# AC_Measurev2_250616.net
KiCad netlist of a schematic drawn in Altium Designer
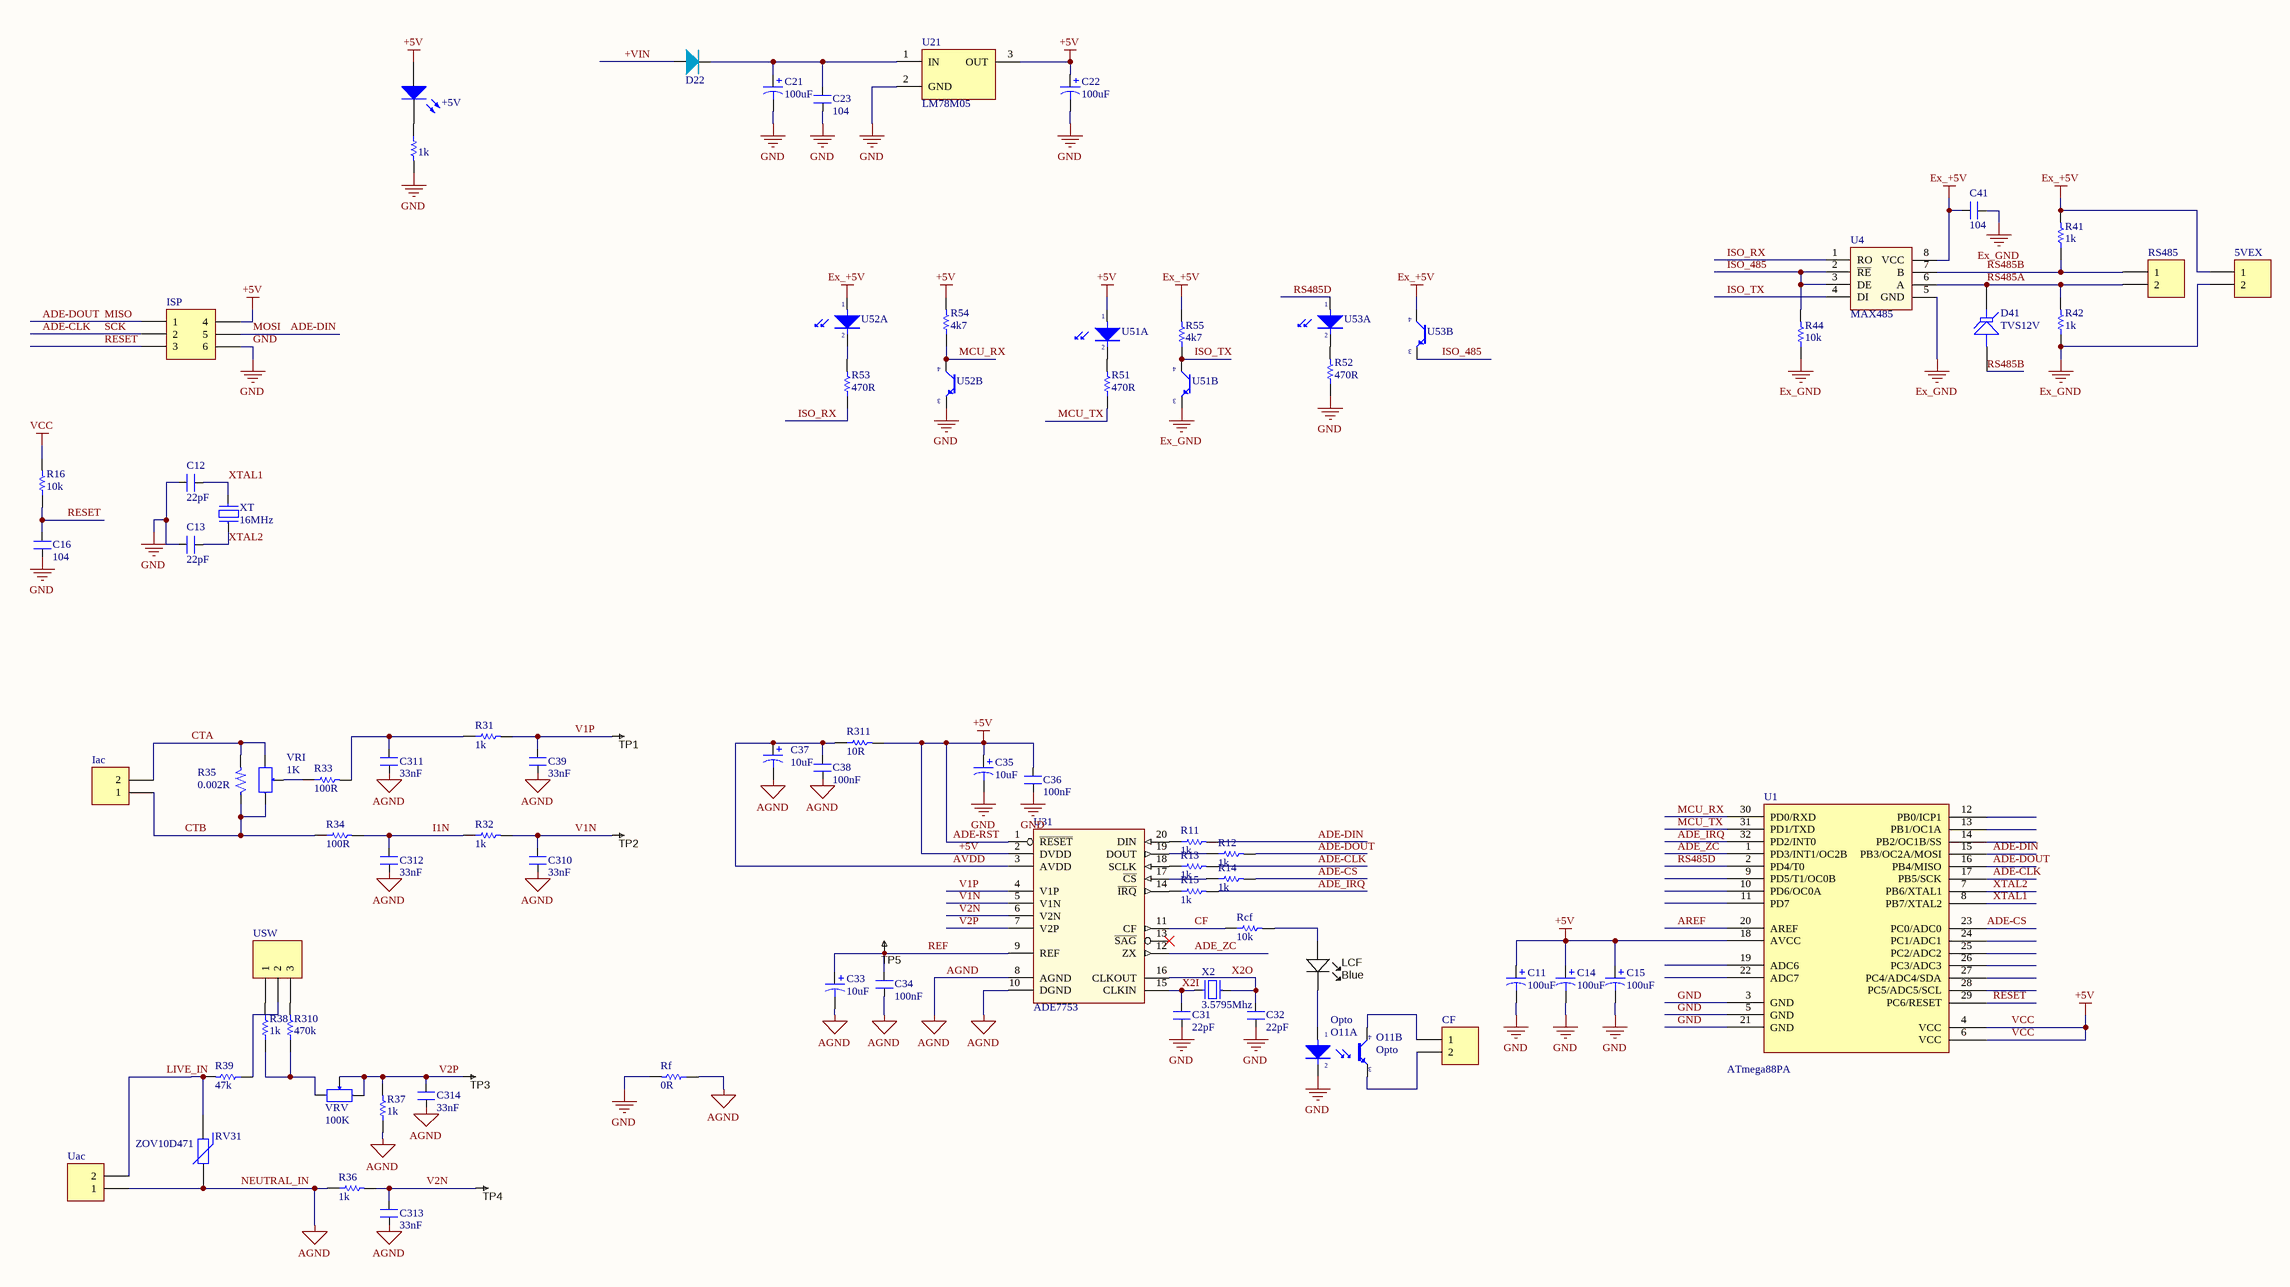
[diagram p0: AC_Measurev2_250616.SchDoc]

(export (version "E")
  (design (tool "Eeschema 10.0.6"))
  (components
    (comp (ref "+5V") (value "Led") (footprint "LED 5mm RED") (libsource (lib "Tuan") (part "Led")))
    (comp (ref "5VEX")
      (value "Header 2")
      (footprint "2P_PCB1")
      (description "Header, 2-Pin")
      (fields (field (name "PUBLISHER") "Altium Limited"))
      (libsource (lib "Miscellaneous Connectors") (part "Header 2"))
    )
    (comp (ref "C11")
      (value "100uF")
      (footprint "CAPC2012N_F")
      (fields (field (name "Comment") "Cap"))
      (libsource (lib "Tuan") (part "Cap"))
    )
    (comp (ref "C12")
      (value "22pF")
      (footprint "CAPC1608N")
      (fields (field (name "Comment") "CAP NP"))
      (libsource (lib "Tuan") (part "CAP NP"))
    )
    (comp (ref "C13")
      (value "22pF")
      (footprint "CAPC1608N")
      (fields (field (name "Comment") "CAP NP"))
      (libsource (lib "Tuan") (part "CAP NP"))
    )
    (comp (ref "C14")
      (value "100uF")
      (footprint "CAPC2012N_F")
      (fields (field (name "Comment") "Cap"))
      (libsource (lib "Tuan") (part "Cap"))
    )
    (comp (ref "C15")
      (value "100uF")
      (footprint "CAPC2012N_F")
      (fields (field (name "Comment") "Cap"))
      (libsource (lib "Tuan") (part "Cap"))
    )
    (comp (ref "C16")
      (value "104")
      (footprint "CAPC1608N")
      (fields (field (name "Comment") "CAP NP"))
      (libsource (lib "Tuan") (part "CAP NP"))
    )
    (comp (ref "C21")
      (value "100uF")
      (footprint "CAP 3.8mm")
      (fields (field (name "Comment") "Cap"))
      (libsource (lib "Tuan") (part "Cap"))
    )
    (comp (ref "C22")
      (value "100uF")
      (footprint "CAP 3.8mm")
      (fields (field (name "Comment") "Cap"))
      (libsource (lib "Tuan") (part "Cap"))
    )
    (comp (ref "C23")
      (value "104")
      (footprint "SMD 1206")
      (fields (field (name "Comment") "CAP NP"))
      (libsource (lib "Tuan") (part "CAP NP"))
    )
    (comp (ref "C31")
      (value "22pF")
      (footprint "CAPC1608N")
      (fields (field (name "Comment") "CAP NP"))
      (libsource (lib "ELS-PLC-2.0") (part "CAP NP"))
    )
    (comp (ref "C32")
      (value "22pF")
      (footprint "CAPC1608N")
      (fields (field (name "Comment") "CAP NP"))
      (libsource (lib "ELS-PLC-2.0") (part "CAP NP"))
    )
    (comp (ref "C33")
      (value "10uF")
      (footprint "CAPC2012N_F")
      (fields (field (name "Comment") "Cap"))
      (libsource (lib "Tuan") (part "Cap"))
    )
    (comp (ref "C34")
      (value "100nF")
      (footprint "CAPC1608N")
      (fields (field (name "Comment") "CAP NP"))
      (libsource (lib "ELS-PLC-2.0") (part "CAP NP"))
    )
    (comp (ref "C35")
      (value "10uF")
      (footprint "CAPC2012N_F")
      (fields (field (name "Comment") "Cap"))
      (libsource (lib "Tuan") (part "Cap"))
    )
    (comp (ref "C36")
      (value "100nF")
      (footprint "CAPC1608N")
      (fields (field (name "Comment") "CAP NP"))
      (libsource (lib "ELS-PLC-2.0") (part "CAP NP"))
    )
    (comp (ref "C37")
      (value "10uF")
      (footprint "CAPC2012N_F")
      (fields (field (name "Comment") "Cap"))
      (libsource (lib "Tuan") (part "Cap"))
    )
    (comp (ref "C38")
      (value "100nF")
      (footprint "CAPC1608N")
      (fields (field (name "Comment") "CAP NP"))
      (libsource (lib "ELS-PLC-2.0") (part "CAP NP"))
    )
    (comp (ref "C39")
      (value "33nF")
      (footprint "CAPC1608N")
      (fields (field (name "Comment") "CAP NP"))
      (libsource (lib "ELS-PLC-2.0") (part "CAP NP"))
    )
    (comp (ref "C41")
      (value "104")
      (footprint "CAPC2012N_F")
      (fields (field (name "Comment") "100nF/104"))
      (libsource (lib "Tuan") (part "CAP NP"))
    )
    (comp (ref "C310")
      (value "33nF")
      (footprint "CAPC1608N")
      (fields (field (name "Comment") "CAP NP"))
      (libsource (lib "ELS-PLC-2.0") (part "CAP NP"))
    )
    (comp (ref "C311")
      (value "33nF")
      (footprint "CAPC1608N")
      (fields (field (name "Comment") "CAP NP"))
      (libsource (lib "ELS-PLC-2.0") (part "CAP NP"))
    )
    (comp (ref "C312")
      (value "33nF")
      (footprint "CAPC1608N")
      (fields (field (name "Comment") "CAP NP"))
      (libsource (lib "ELS-PLC-2.0") (part "CAP NP"))
    )
    (comp (ref "C313")
      (value "33nF")
      (footprint "CAPC2012N_F")
      (fields (field (name "Comment") "CAP NP"))
      (libsource (lib "ELS-PLC-2.0") (part "CAP NP"))
    )
    (comp (ref "C314")
      (value "33nF")
      (footprint "CAPC2012N_F")
      (fields (field (name "Comment") "CAP NP"))
      (libsource (lib "ELS-PLC-2.0") (part "CAP NP"))
    )
    (comp (ref "CF")
      (value "Header 2")
      (footprint "2P_PCB1")
      (description "Header, 2-Pin")
      (fields (field (name "PUBLISHER") "Altium Limited"))
      (libsource (lib "Miscellaneous Connectors") (part "Header 2"))
    )
    (comp (ref "D22") (value "Diode") (footprint "DO-214AC") (libsource (lib "Tuan") (part "Diode")))
    (comp (ref "D41")
      (value "TVS12V")
      (footprint "DO-214AA")
      (description "Transient Voltage Suppression (TVS) Diode")
      (fields (field (name "PUBLISHER") "Altium Limited"))
      (libsource (lib "Miscellaneous Devices") (part "Tranzorb"))
    )
    (comp (ref "Iac")
      (value "Header 2")
      (footprint "2P_PCB1")
      (description "Header, 2-Pin")
      (fields (field (name "PUBLISHER") "Altium Limited"))
      (libsource (lib "") (part "Header 2_1"))
    )
    (comp (ref "ISP")
      (value "Header 3X2A")
      (footprint "HDR2X3_CEN")
      (description "Header, 3-Pin, Dual row")
      (fields (field (name "PUBLISHER") "Altium Limited"))
      (libsource (lib "Miscellaneous Connectors") (part "Header 3X2A"))
    )
    (comp (ref "LCF")
      (value "Blue")
      (footprint "LED-0805-K")
      (description "LED 0805 SMD Blue 100mcd 470nm")
      (fields (field (name "COLOR") "Blue"))
      (libsource (lib "PBL - Light Sources") (part "LED_SMD_Blue_0805_100mcd"))
    )
    (comp (ref "O11") (value "Opto") (footprint "DIP4/W0.3") (libsource (lib "Tuan") (part "Opto")))
    (comp (ref "R11")
      (value "1k")
      (footprint "RESC1608N_F")
      (fields (field (name "Comment") "Res"))
      (libsource (lib "Tuan") (part "Res"))
    )
    (comp (ref "R12")
      (value "1k")
      (footprint "RESC1608N_F")
      (fields (field (name "Comment") "Res"))
      (libsource (lib "Tuan") (part "Res"))
    )
    (comp (ref "R13")
      (value "1k")
      (footprint "RESC1608N_F")
      (fields (field (name "Comment") "Res"))
      (libsource (lib "Tuan") (part "Res"))
    )
    (comp (ref "R14")
      (value "1k")
      (footprint "RESC1608N_F")
      (fields (field (name "Comment") "Res"))
      (libsource (lib "Tuan") (part "Res"))
    )
    (comp (ref "R15")
      (value "1k")
      (footprint "RESC1608N_F")
      (fields (field (name "Comment") "Res"))
      (libsource (lib "Tuan") (part "Res"))
    )
    (comp (ref "R16")
      (value "10k")
      (footprint "RESC1608N_F")
      (fields (field (name "Comment") "Res"))
      (libsource (lib "Tuan") (part "Res"))
    )
    (comp (ref "R22")
      (value "1k")
      (footprint "RESC2012N_F")
      (fields (field (name "Comment") "Res_0805_1k"))
      (libsource (lib "Tuan") (part "Res"))
    )
    (comp (ref "R31")
      (value "1k")
      (footprint "0603ESDA")
      (fields (field (name "Comment") "Res"))
      (libsource (lib "Tuan") (part "Res"))
    )
    (comp (ref "R32")
      (value "1k")
      (footprint "0603ESDA")
      (fields (field (name "Comment") "Res"))
      (libsource (lib "Tuan") (part "Res"))
    )
    (comp (ref "R33")
      (value "100R")
      (footprint "0603ESDA")
      (fields (field (name "Comment") "Res"))
      (libsource (lib "Tuan") (part "Res"))
    )
    (comp (ref "R34")
      (value "100R")
      (footprint "0603ESDA")
      (fields (field (name "Comment") "Res"))
      (libsource (lib "Tuan") (part "Res"))
    )
    (comp (ref "R35")
      (value "0.002R")
      (footprint "RESC6332N")
      (description "Resistor 1/4W")
      (libsource (lib "syhaunguyen") (part "R"))
    )
    (comp (ref "R36")
      (value "1k")
      (footprint "RESC2012N_F")
      (fields (field (name "Comment") "Res"))
      (libsource (lib "Tuan") (part "Res"))
    )
    (comp (ref "R37")
      (value "1k")
      (footprint "RESC2012N_F")
      (fields (field (name "Comment") "Res"))
      (libsource (lib "Tuan") (part "Res"))
    )
    (comp (ref "R38")
      (value "1k")
      (footprint "RESC2012N_F")
      (fields (field (name "Comment") "Res"))
      (libsource (lib "Tuan") (part "Res"))
    )
    (comp (ref "R39")
      (value "47k")
      (footprint "RESC2012N_F")
      (fields (field (name "Comment") "Res"))
      (libsource (lib "Tuan") (part "Res"))
    )
    (comp (ref "R41")
      (value "1k")
      (footprint "RESC1608N_ZERO")
      (description "Tro dan")
      (libsource (lib "GPS_Clock_v12") (part "Res"))
    )
    (comp (ref "R42")
      (value "1k")
      (footprint "RESC1608N_ZERO")
      (description "Tro dan")
      (libsource (lib "GPS_Clock_v12") (part "Res"))
    )
    (comp (ref "R44")
      (value "10k")
      (footprint "RESC1608N_ZERO")
      (description "Tro dan")
      (fields (field (name "Comment") "330R"))
      (libsource (lib "GPS_Clock_v12") (part "Res"))
    )
    (comp (ref "R51")
      (value "470R")
      (footprint "RESC2012N_F")
      (fields (field (name "Comment") "Res"))
      (libsource (lib "Tuan") (part "Res"))
    )
    (comp (ref "R52")
      (value "470R")
      (footprint "RESC2012N_F")
      (fields (field (name "Comment") "Res"))
      (libsource (lib "Tuan") (part "Res"))
    )
    (comp (ref "R53")
      (value "470R")
      (footprint "RESC2012N_F")
      (fields (field (name "Comment") "Res"))
      (libsource (lib "Tuan") (part "Res"))
    )
    (comp (ref "R54")
      (value "4k7")
      (footprint "RESC2012N_F")
      (fields (field (name "Comment") "Res"))
      (libsource (lib "Tuan") (part "Res"))
    )
    (comp (ref "R55")
      (value "4k7")
      (footprint "RESC2012N_F")
      (fields (field (name "Comment") "Res"))
      (libsource (lib "Tuan") (part "Res"))
    )
    (comp (ref "R310")
      (value "470k")
      (footprint "RESC2012N_F")
      (fields (field (name "Comment") "Res"))
      (libsource (lib "Tuan") (part "Res"))
    )
    (comp (ref "R311")
      (value "10R")
      (footprint "RESC2012N_F")
      (fields (field (name "Comment") "Res"))
      (libsource (lib "Tuan") (part "Res"))
    )
    (comp (ref "Rcf")
      (value "10k")
      (footprint "RESC1608N_F")
      (fields (field (name "Comment") "Res"))
      (libsource (lib "Tuan") (part "Res"))
    )
    (comp (ref "Rf")
      (value "0R")
      (footprint "RESC2012N_F")
      (fields (field (name "Comment") "Res"))
      (libsource (lib "Tuan") (part "Res"))
    )
    (comp (ref "RS485")
      (value "Header 2")
      (footprint "2P_PCB1")
      (description "Header, 2-Pin")
      (fields (field (name "PUBLISHER") "Altium Limited"))
      (libsource (lib "Miscellaneous Connectors") (part "Header 2"))
    )
    (comp (ref "RV31")
      (value "ZOV10D471")
      (footprint "CN3")
      (description "Varistor (Voltage-Sensitive Resistor)")
      (fields (field (name "PUBLISHER") "Altium Limited"))
      (libsource (lib "Miscellaneous Devices") (part "Res Varistor"))
    )
    (comp (ref "TP1")
      (value "TESTPOINT")
      (footprint "TP-R60")
      (description "SMD test pin")
      (libsource (lib "PBL - Test Points") (part "TESTPOINT"))
    )
    (comp (ref "TP2")
      (value "TESTPOINT")
      (footprint "TP-R60")
      (description "SMD test pin")
      (libsource (lib "PBL - Test Points") (part "TESTPOINT"))
    )
    (comp (ref "TP3")
      (value "TESTPOINT")
      (footprint "TP-R60")
      (description "SMD test pin")
      (libsource (lib "PBL - Test Points") (part "TESTPOINT"))
    )
    (comp (ref "TP4")
      (value "TESTPOINT")
      (footprint "TP-R60")
      (description "SMD test pin")
      (libsource (lib "PBL - Test Points") (part "TESTPOINT"))
    )
    (comp (ref "TP5")
      (value "TESTPOINT")
      (footprint "TP-R60")
      (description "SMD test pin")
      (libsource (lib "PBL - Test Points") (part "TESTPOINT"))
    )
    (comp (ref "U1")
      (value "ATmega88PA")
      (footprint "32PIN")
      (description "ATmega48/168/328")
      (libsource (lib "Tuan") (part "ATmega48/168/328"))
    )
    (comp (ref "U4")
      (value "MAX485")
      (footprint "SO-8")
      (description "RS232 - RS485 (Same sn75176)")
      (libsource (lib "heromap") (part "MAX485"))
    )
    (comp (ref "U21") (value "LM78M05") (footprint "TO252 D-PAK") (libsource (lib "Tuan") (part "LM78xx")))
    (comp (ref "U31")
      (value "ADE7753")
      (footprint "TSSOP-20")
      (description "Single-Phase Multifunction Metering IC with di/dt Sensor Interface")
      (libsource (lib "heromap") (part "ADE7753"))
    )
    (comp (ref "U51") (value "Opto") (footprint "DIP4/W0.3") (libsource (lib "Tuan") (part "Opto")))
    (comp (ref "U52") (value "Opto") (footprint "DIP4/W0.3") (libsource (lib "Tuan") (part "Opto")))
    (comp (ref "U53") (value "Opto") (footprint "DIP4/W0.3") (libsource (lib "Tuan") (part "Opto")))
    (comp (ref "Uac")
      (value "Header 2")
      (footprint "2P_PCB1")
      (description "Header, 2-Pin")
      (fields (field (name "PUBLISHER") "Altium Limited"))
      (libsource (lib "") (part "Header 2_1"))
    )
    (comp (ref "USW")
      (value "Header 3")
      (footprint "HDR1X3")
      (description "Header, 3-Pin")
      (fields (field (name "PUBLISHER") "Altium Limited"))
      (libsource (lib "Miscellaneous Connectors") (part "Header 3"))
    )
    (comp (ref "VRI")
      (value "1K")
      (footprint "heromap:VR1")
      (description "Var Resistor")
      (libsource (lib "heromap") (part "VR"))
    )
    (comp (ref "VRV")
      (value "100K")
      (footprint "heromap:VR1")
      (description "Var Resistor")
      (libsource (lib "heromap") (part "VR"))
    )
    (comp (ref "X2")
      (value "3.5795Mhz")
      (footprint "heromap:XT2")
      (description "Crystal For all Crystal 2pin.")
      (libsource (lib "heromap") (part "XT2"))
    )
    (comp (ref "XT") (value "16MHz") (footprint "XT2") (libsource (lib "Tuan") (part "Crystal")))
  )
  (nets
    (net (code "1") (name "+5V") (class "Default")
      (node (ref "+5V") (pin "1") (pinfunction "A_1") (pintype "passive"))
      (node (ref "C11") (pin "1") (pinfunction "1_1") (pintype "passive"))
      (node (ref "C14") (pin "1") (pinfunction "1_1") (pintype "passive"))
      (node (ref "C15") (pin "1") (pinfunction "1_1") (pintype "passive"))
      (node (ref "C22") (pin "1") (pinfunction "1_1") (pintype "passive"))
      (node (ref "C35") (pin "1") (pinfunction "1_1") (pintype "passive"))
      (node (ref "C36") (pin "2") (pinfunction "2_2") (pintype "passive"))
      (node (ref "ISP") (pin "4") (pinfunction "4_4") (pintype "passive"))
      (node (ref "R16") (pin "2") (pinfunction "2_2") (pintype "passive"))
      (node (ref "R311") (pin "2") (pinfunction "2_2") (pintype "passive"))
      (node (ref "R54") (pin "2") (pinfunction "2_2") (pintype "passive"))
      (node (ref "U1") (pin "18") (pinfunction "AVCC_18") (pintype "passive"))
      (node (ref "U1") (pin "4") (pinfunction "VCC_4") (pintype "passive"))
      (node (ref "U1") (pin "6") (pinfunction "VCC_6") (pintype "passive"))
      (node (ref "U21") (pin "3") (pinfunction "OUT_3") (pintype "passive"))
      (node (ref "U31") (pin "1") (pinfunction "~{RESET}_1") (pintype "passive"))
      (node (ref "U31") (pin "2") (pinfunction "DVDD_2") (pintype "passive"))
      (node (ref "U51") (pin "1") (pinfunction "A_1") (pintype "passive"))
    )
    (net (code "2") (name "/+VIN") (class "Default")
      (node (ref "D22") (pin "1") (pinfunction "A_1") (pintype "passive"))
    )
    (net (code "3") (name "/ADE-CLK") (class "Default")
      (node (ref "ISP") (pin "2") (pinfunction "2_2") (pintype "passive"))
      (node (ref "R13") (pin "2") (pinfunction "2_2") (pintype "passive"))
      (node (ref "U1") (pin "17") (pinfunction "PB5/SCK_17") (pintype "passive"))
    )
    (net (code "4") (name "/ADE-CS") (class "Default")
      (node (ref "R14") (pin "2") (pinfunction "2_2") (pintype "passive"))
      (node (ref "U1") (pin "23") (pinfunction "PC0/ADC0_23") (pintype "passive"))
    )
    (net (code "5") (name "/ADE-DIN") (class "Default")
      (node (ref "ISP") (pin "5") (pinfunction "5_5") (pintype "passive"))
      (node (ref "R11") (pin "2") (pinfunction "2_2") (pintype "passive"))
      (node (ref "U1") (pin "15") (pinfunction "PB3/OC2A/MOSI_15") (pintype "passive"))
    )
    (net (code "6") (name "/ADE-DOUT") (class "Default")
      (node (ref "ISP") (pin "1") (pinfunction "1_1") (pintype "passive"))
      (node (ref "R12") (pin "2") (pinfunction "2_2") (pintype "passive"))
      (node (ref "U1") (pin "16") (pinfunction "PB4/MISO_16") (pintype "passive"))
    )
    (net (code "7") (name "/ADE_IRQ") (class "Default")
      (node (ref "R15") (pin "2") (pinfunction "2_2") (pintype "passive"))
      (node (ref "U1") (pin "32") (pinfunction "PD2/INT0_32") (pintype "passive"))
    )
    (net (code "8") (name "/ADE_ZC") (class "Default")
      (node (ref "U1") (pin "1") (pinfunction "PD3/INT1/OC2B_1") (pintype "passive"))
      (node (ref "U31") (pin "12") (pinfunction "ZX_12") (pintype "output"))
    )
    (net (code "9") (name "/AREF") (class "Default")
      (node (ref "U1") (pin "20") (pinfunction "AREF_20") (pintype "passive"))
    )
    (net (code "10") (name "/AVDD") (class "Default")
      (node (ref "C37") (pin "1") (pinfunction "1_1") (pintype "passive"))
      (node (ref "C38") (pin "2") (pinfunction "2_2") (pintype "passive"))
      (node (ref "R311") (pin "1") (pinfunction "1_1") (pintype "passive"))
      (node (ref "U31") (pin "3") (pinfunction "AVDD_3") (pintype "passive"))
    )
    (net (code "11") (name "/CF") (class "Default")
      (node (ref "Rcf") (pin "1") (pinfunction "1_1") (pintype "passive"))
      (node (ref "U31") (pin "11") (pinfunction "CF_11") (pintype "output"))
    )
    (net (code "12") (name "/CTA") (class "Default")
      (node (ref "Iac") (pin "2") (pinfunction "2_2") (pintype "passive"))
      (node (ref "R35") (pin "2") (pinfunction "2_2") (pintype "passive"))
      (node (ref "VRI") (pin "1") (pinfunction "1_1") (pintype "passive"))
    )
    (net (code "13") (name "/CTB") (class "Default")
      (node (ref "Iac") (pin "1") (pinfunction "1_1") (pintype "passive"))
      (node (ref "R34") (pin "1") (pinfunction "1_1") (pintype "passive"))
      (node (ref "R35") (pin "1") (pinfunction "1_1") (pintype "passive"))
      (node (ref "VRI") (pin "3") (pinfunction "3_3") (pintype "passive"))
    )
    (net (code "14") (name "/I1N") (class "Default")
      (node (ref "C312") (pin "2") (pinfunction "2_2") (pintype "passive"))
      (node (ref "R32") (pin "1") (pinfunction "1_1") (pintype "passive"))
      (node (ref "R34") (pin "2") (pinfunction "2_2") (pintype "passive"))
    )
    (net (code "15") (name "/ISO_485") (class "Default")
      (node (ref "R44") (pin "2") (pinfunction "2_2") (pintype "passive"))
      (node (ref "U4") (pin "2") (pinfunction "~{RE}_2") (pintype "passive"))
      (node (ref "U4") (pin "3") (pinfunction "DE_3") (pintype "passive"))
      (node (ref "U53") (pin "3") (pinfunction "E_3") (pintype "passive"))
    )
    (net (code "16") (name "/ISO_RX") (class "Default")
      (node (ref "R53") (pin "1") (pinfunction "1_1") (pintype "passive"))
      (node (ref "U4") (pin "1") (pinfunction "RO_1") (pintype "passive"))
    )
    (net (code "17") (name "/ISO_TX") (class "Default")
      (node (ref "R55") (pin "1") (pinfunction "1_1") (pintype "passive"))
      (node (ref "U4") (pin "4") (pinfunction "DI_4") (pintype "passive"))
      (node (ref "U51") (pin "4") (pinfunction "C_4") (pintype "passive"))
    )
    (net (code "18") (name "/LIVE_IN") (class "Default")
      (node (ref "R39") (pin "2") (pinfunction "2_2") (pintype "passive"))
      (node (ref "RV31") (pin "1") (pinfunction "1_1") (pintype "passive"))
      (node (ref "Uac") (pin "2") (pinfunction "2_2") (pintype "passive"))
    )
    (net (code "19") (name "/MCU_RX") (class "Default")
      (node (ref "R54") (pin "1") (pinfunction "1_1") (pintype "passive"))
      (node (ref "U1") (pin "30") (pinfunction "PD0/RXD_30") (pintype "passive"))
      (node (ref "U52") (pin "4") (pinfunction "C_4") (pintype "passive"))
    )
    (net (code "20") (name "/MCU_TX") (class "Default")
      (node (ref "R51") (pin "1") (pinfunction "1_1") (pintype "passive"))
      (node (ref "U1") (pin "31") (pinfunction "PD1/TXD_31") (pintype "passive"))
    )
    (net (code "21") (name "/REF") (class "Default")
      (node (ref "C33") (pin "1") (pinfunction "1_1") (pintype "passive"))
      (node (ref "C34") (pin "2") (pinfunction "2_2") (pintype "passive"))
      (node (ref "TP5") (pin "1") (pintype "passive"))
      (node (ref "U31") (pin "9") (pinfunction "REF_9") (pintype "passive"))
    )
    (net (code "22") (name "/RESET") (class "Default")
      (node (ref "C16") (pin "2") (pinfunction "2_2") (pintype "passive"))
      (node (ref "ISP") (pin "3") (pinfunction "3_3") (pintype "passive"))
      (node (ref "R16") (pin "1") (pinfunction "1_1") (pintype "passive"))
      (node (ref "U1") (pin "29") (pinfunction "PC6/RESET_29") (pintype "passive"))
    )
    (net (code "23") (name "/RS485A") (class "Default")
      (node (ref "D41") (pin "2") (pinfunction "K_2") (pintype "passive"))
      (node (ref "R42") (pin "2") (pinfunction "2_2") (pintype "passive"))
      (node (ref "RS485") (pin "2") (pinfunction "2_2") (pintype "passive"))
      (node (ref "U4") (pin "6") (pinfunction "A_6") (pintype "passive"))
    )
    (net (code "24") (name "/RS485B") (class "Default")
      (node (ref "D41") (pin "1") (pinfunction "A_1") (pintype "passive"))
      (node (ref "R41") (pin "1") (pinfunction "1_1") (pintype "passive"))
      (node (ref "RS485") (pin "1") (pinfunction "1_1") (pintype "passive"))
      (node (ref "U4") (pin "7") (pinfunction "B_7") (pintype "passive"))
    )
    (net (code "25") (name "/RS485D") (class "Default")
      (node (ref "U1") (pin "2") (pinfunction "PD4/T0_2") (pintype "passive"))
      (node (ref "U53") (pin "1") (pinfunction "A_1") (pintype "passive"))
    )
    (net (code "26") (name "/V1N") (class "Default")
      (node (ref "C310") (pin "2") (pinfunction "2_2") (pintype "passive"))
      (node (ref "R32") (pin "2") (pinfunction "2_2") (pintype "passive"))
      (node (ref "TP2") (pin "1") (pintype "passive"))
      (node (ref "U31") (pin "5") (pinfunction "V1N_5") (pintype "passive"))
    )
    (net (code "27") (name "/V1P") (class "Default")
      (node (ref "C39") (pin "2") (pinfunction "2_2") (pintype "passive"))
      (node (ref "R31") (pin "2") (pinfunction "2_2") (pintype "passive"))
      (node (ref "TP1") (pin "1") (pintype "passive"))
      (node (ref "U31") (pin "4") (pinfunction "V1P_4") (pintype "passive"))
    )
    (net (code "28") (name "/V2N") (class "Default")
      (node (ref "C313") (pin "2") (pinfunction "2_2") (pintype "passive"))
      (node (ref "R36") (pin "2") (pinfunction "2_2") (pintype "passive"))
      (node (ref "TP4") (pin "1") (pintype "passive"))
      (node (ref "U31") (pin "6") (pinfunction "V2N_6") (pintype "passive"))
    )
    (net (code "29") (name "/V2P") (class "Default")
      (node (ref "C314") (pin "2") (pinfunction "2_2") (pintype "passive"))
      (node (ref "R37") (pin "2") (pinfunction "2_2") (pintype "passive"))
      (node (ref "TP3") (pin "1") (pintype "passive"))
      (node (ref "U31") (pin "7") (pinfunction "V2P_7") (pintype "passive"))
      (node (ref "VRV") (pin "2") (pinfunction "2_2") (pintype "passive"))
      (node (ref "VRV") (pin "3") (pinfunction "3_3") (pintype "passive"))
    )
    (net (code "30") (name "/X2I") (class "Default")
      (node (ref "C31") (pin "2") (pinfunction "2_2") (pintype "passive"))
      (node (ref "U31") (pin "15") (pinfunction "CLKIN_15") (pintype "passive"))
      (node (ref "X2") (pin "2") (pinfunction "2_2") (pintype "passive"))
    )
    (net (code "31") (name "/X2O") (class "Default")
      (node (ref "C32") (pin "2") (pinfunction "2_2") (pintype "passive"))
      (node (ref "U31") (pin "16") (pinfunction "CLKOUT_16") (pintype "passive"))
      (node (ref "X2") (pin "1") (pinfunction "1_1") (pintype "passive"))
    )
    (net (code "32") (name "/XTAL1") (class "Default")
      (node (ref "C12") (pin "1") (pinfunction "1_1") (pintype "passive"))
      (node (ref "U1") (pin "8") (pinfunction "PB7/XTAL2_8") (pintype "passive"))
      (node (ref "XT") (pin "2") (pinfunction "2_2") (pintype "passive"))
    )
    (net (code "33") (name "/XTAL2") (class "Default")
      (node (ref "C13") (pin "1") (pinfunction "1_1") (pintype "passive"))
      (node (ref "U1") (pin "7") (pinfunction "PB6/XTAL1_7") (pintype "passive"))
      (node (ref "XT") (pin "1") (pinfunction "1_1") (pintype "passive"))
    )
    (net (code "34") (name "AGND") (class "Default")
      (node (ref "C310") (pin "1") (pinfunction "1_1") (pintype "passive"))
      (node (ref "C311") (pin "1") (pinfunction "1_1") (pintype "passive"))
      (node (ref "C312") (pin "1") (pinfunction "1_1") (pintype "passive"))
      (node (ref "C313") (pin "1") (pinfunction "1_1") (pintype "passive"))
      (node (ref "C314") (pin "1") (pinfunction "1_1") (pintype "passive"))
      (node (ref "C33") (pin "2") (pinfunction "2_2") (pintype "passive"))
      (node (ref "C34") (pin "1") (pinfunction "1_1") (pintype "passive"))
      (node (ref "C37") (pin "2") (pinfunction "2_2") (pintype "passive"))
      (node (ref "C38") (pin "1") (pinfunction "1_1") (pintype "passive"))
      (node (ref "C39") (pin "1") (pinfunction "1_1") (pintype "passive"))
      (node (ref "R36") (pin "1") (pinfunction "1_1") (pintype "passive"))
      (node (ref "R37") (pin "1") (pinfunction "1_1") (pintype "passive"))
      (node (ref "RV31") (pin "2") (pinfunction "2_2") (pintype "passive"))
      (node (ref "Rf") (pin "1") (pinfunction "1_1") (pintype "passive"))
      (node (ref "U31") (pin "10") (pinfunction "DGND_10") (pintype "passive"))
      (node (ref "U31") (pin "8") (pinfunction "AGND_8") (pintype "passive"))
      (node (ref "Uac") (pin "1") (pinfunction "1_1") (pintype "passive"))
    )
    (net (code "35") (name "Ex_+5V") (class "Default")
      (node (ref "5VEX") (pin "1") (pinfunction "1_1") (pintype "passive"))
      (node (ref "C41") (pin "2") (pinfunction "2_2") (pintype "passive"))
      (node (ref "R41") (pin "2") (pinfunction "2_2") (pintype "passive"))
      (node (ref "R55") (pin "2") (pinfunction "2_2") (pintype "passive"))
      (node (ref "U4") (pin "8") (pinfunction "VCC_8") (pintype "passive"))
      (node (ref "U52") (pin "1") (pinfunction "A_1") (pintype "passive"))
      (node (ref "U53") (pin "4") (pinfunction "C_4") (pintype "passive"))
    )
    (net (code "36") (name "Ex_GND") (class "Default")
      (node (ref "5VEX") (pin "2") (pinfunction "2_2") (pintype "passive"))
      (node (ref "C41") (pin "1") (pinfunction "1_1") (pintype "passive"))
      (node (ref "R42") (pin "1") (pinfunction "1_1") (pintype "passive"))
      (node (ref "R44") (pin "1") (pinfunction "1_1") (pintype "passive"))
      (node (ref "U4") (pin "5") (pinfunction "GND_5") (pintype "passive"))
      (node (ref "U51") (pin "3") (pinfunction "E_3") (pintype "passive"))
    )
    (net (code "37") (name "GND") (class "Default")
      (node (ref "C11") (pin "2") (pinfunction "2_2") (pintype "passive"))
      (node (ref "C12") (pin "2") (pinfunction "2_2") (pintype "passive"))
      (node (ref "C13") (pin "2") (pinfunction "2_2") (pintype "passive"))
      (node (ref "C14") (pin "2") (pinfunction "2_2") (pintype "passive"))
      (node (ref "C15") (pin "2") (pinfunction "2_2") (pintype "passive"))
      (node (ref "C16") (pin "1") (pinfunction "1_1") (pintype "passive"))
      (node (ref "C21") (pin "2") (pinfunction "2_2") (pintype "passive"))
      (node (ref "C22") (pin "2") (pinfunction "2_2") (pintype "passive"))
      (node (ref "C23") (pin "1") (pinfunction "1_1") (pintype "passive"))
      (node (ref "C31") (pin "1") (pinfunction "1_1") (pintype "passive"))
      (node (ref "C32") (pin "1") (pinfunction "1_1") (pintype "passive"))
      (node (ref "C35") (pin "2") (pinfunction "2_2") (pintype "passive"))
      (node (ref "C36") (pin "1") (pinfunction "1_1") (pintype "passive"))
      (node (ref "ISP") (pin "6") (pinfunction "6_6") (pintype "passive"))
      (node (ref "O11") (pin "2") (pinfunction "K_2") (pintype "passive"))
      (node (ref "R22") (pin "2") (pinfunction "2_2") (pintype "passive"))
      (node (ref "R52") (pin "1") (pinfunction "1_1") (pintype "passive"))
      (node (ref "Rf") (pin "2") (pinfunction "2_2") (pintype "passive"))
      (node (ref "U1") (pin "21") (pinfunction "GND_21") (pintype "power_in"))
      (node (ref "U1") (pin "3") (pinfunction "GND_3") (pintype "power_in"))
      (node (ref "U1") (pin "5") (pinfunction "GND_5") (pintype "power_in"))
      (node (ref "U21") (pin "2") (pinfunction "GND_2") (pintype "passive"))
      (node (ref "U52") (pin "3") (pinfunction "E_3") (pintype "passive"))
    )
    (net (code "38") (name "Net-(+5V-K)") (class "Default")
      (node (ref "+5V") (pin "2") (pinfunction "K_2") (pintype "passive"))
      (node (ref "R22") (pin "1") (pinfunction "1_1") (pintype "passive"))
    )
    (net (code "39") (name "Net-(C311-Pad2)") (class "Default")
      (node (ref "C311") (pin "2") (pinfunction "2_2") (pintype "passive"))
      (node (ref "R31") (pin "1") (pinfunction "1_1") (pintype "passive"))
      (node (ref "R33") (pin "2") (pinfunction "2_2") (pintype "passive"))
    )
    (net (code "40") (name "Net-(D22-K)") (class "Default")
      (node (ref "C21") (pin "1") (pinfunction "1_1") (pintype "passive"))
      (node (ref "C23") (pin "2") (pinfunction "2_2") (pintype "passive"))
      (node (ref "D22") (pin "2") (pinfunction "K_2") (pintype "passive"))
      (node (ref "U21") (pin "1") (pinfunction "IN_1") (pintype "passive"))
    )
    (net (code "41") (name "Net-(LCF-PadA)") (class "Default")
      (node (ref "LCF") (pin "A") (pinfunction "A_A") (pintype "passive"))
      (node (ref "Rcf") (pin "2") (pinfunction "2_2") (pintype "passive"))
    )
    (net (code "42") (name "Net-(O11A-A)") (class "Default")
      (node (ref "LCF") (pin "K") (pinfunction "K_K") (pintype "passive"))
      (node (ref "O11") (pin "1") (pinfunction "A_1") (pintype "passive"))
    )
    (net (code "43") (name "Net-(O11B-C)") (class "Default")
      (node (ref "CF") (pin "1") (pinfunction "1_1") (pintype "passive"))
      (node (ref "O11") (pin "4") (pinfunction "C_4") (pintype "passive"))
    )
    (net (code "44") (name "Net-(O11B-E)") (class "Default")
      (node (ref "CF") (pin "2") (pinfunction "2_2") (pintype "passive"))
      (node (ref "O11") (pin "3") (pinfunction "E_3") (pintype "passive"))
    )
    (net (code "45") (name "Net-(R33-Pad1)") (class "Default")
      (node (ref "R33") (pin "1") (pinfunction "1_1") (pintype "passive"))
      (node (ref "VRI") (pin "2") (pinfunction "2_2") (pintype "passive"))
    )
    (net (code "46") (name "Net-(R38-Pad2)") (class "Default")
      (node (ref "R38") (pin "2") (pinfunction "2_2") (pintype "passive"))
      (node (ref "USW") (pin "1") (pinfunction "1_1") (pintype "passive"))
    )
    (net (code "47") (name "Net-(R39-Pad1)") (class "Default")
      (node (ref "R39") (pin "1") (pinfunction "1_1") (pintype "passive"))
      (node (ref "USW") (pin "2") (pinfunction "2_2") (pintype "passive"))
    )
    (net (code "48") (name "Net-(R310-Pad1)") (class "Default")
      (node (ref "R310") (pin "1") (pinfunction "1_1") (pintype "passive"))
      (node (ref "R38") (pin "1") (pinfunction "1_1") (pintype "passive"))
      (node (ref "VRV") (pin "1") (pinfunction "1_1") (pintype "passive"))
    )
    (net (code "49") (name "Net-(R310-Pad2)") (class "Default")
      (node (ref "R310") (pin "2") (pinfunction "2_2") (pintype "passive"))
      (node (ref "USW") (pin "3") (pinfunction "3_3") (pintype "passive"))
    )
    (net (code "50") (name "Net-(U31-DIN)") (class "Default")
      (node (ref "R11") (pin "1") (pinfunction "1_1") (pintype "passive"))
      (node (ref "U31") (pin "20") (pinfunction "DIN_20") (pintype "input"))
    )
    (net (code "51") (name "Net-(U31-DOUT)") (class "Default")
      (node (ref "R12") (pin "1") (pinfunction "1_1") (pintype "passive"))
      (node (ref "U31") (pin "19") (pinfunction "DOUT_19") (pintype "output"))
    )
    (net (code "52") (name "Net-(U31-SCLK)") (class "Default")
      (node (ref "R13") (pin "1") (pinfunction "1_1") (pintype "passive"))
      (node (ref "U31") (pin "18") (pinfunction "SCLK_18") (pintype "input"))
    )
    (net (code "53") (name "Net-(U31-~{CS})") (class "Default")
      (node (ref "R14") (pin "1") (pinfunction "1_1") (pintype "passive"))
      (node (ref "U31") (pin "17") (pinfunction "~{CS}_17") (pintype "input"))
    )
    (net (code "54") (name "Net-(U31-~{IRQ})") (class "Default")
      (node (ref "R15") (pin "1") (pinfunction "1_1") (pintype "passive"))
      (node (ref "U31") (pin "14") (pinfunction "~{IRQ}_14") (pintype "output"))
    )
    (net (code "55") (name "Net-(U51A-K)") (class "Default")
      (node (ref "R51") (pin "2") (pinfunction "2_2") (pintype "passive"))
      (node (ref "U51") (pin "2") (pinfunction "K_2") (pintype "passive"))
    )
    (net (code "56") (name "Net-(U52A-K)") (class "Default")
      (node (ref "R53") (pin "2") (pinfunction "2_2") (pintype "passive"))
      (node (ref "U52") (pin "2") (pinfunction "K_2") (pintype "passive"))
    )
    (net (code "57") (name "Net-(U53A-K)") (class "Default")
      (node (ref "R52") (pin "2") (pinfunction "2_2") (pintype "passive"))
      (node (ref "U53") (pin "2") (pinfunction "K_2") (pintype "passive"))
    )
    (net (code "58") (name "unconnected-(U1-ADC6-Pad19)") (class "Default")
      (node (ref "U1") (pin "19") (pinfunction "ADC6_19") (pintype "passive"))
    )
    (net (code "59") (name "unconnected-(U1-ADC7-Pad22)") (class "Default")
      (node (ref "U1") (pin "22") (pinfunction "ADC7_22") (pintype "passive"))
    )
    (net (code "60") (name "unconnected-(U1-PB0{slash}ICP1-Pad12)") (class "Default")
      (node (ref "U1") (pin "12") (pinfunction "PB0/ICP1_12") (pintype "passive"))
    )
    (net (code "61") (name "unconnected-(U1-PB1{slash}OC1A-Pad13)") (class "Default")
      (node (ref "U1") (pin "13") (pinfunction "PB1/OC1A_13") (pintype "passive"))
    )
    (net (code "62") (name "unconnected-(U1-PB2{slash}OC1B{slash}SS-Pad14)") (class "Default")
      (node (ref "U1") (pin "14") (pinfunction "PB2/OC1B/SS_14") (pintype "passive"))
    )
    (net (code "63") (name "unconnected-(U1-PC1{slash}ADC1-Pad24)") (class "Default")
      (node (ref "U1") (pin "24") (pinfunction "PC1/ADC1_24") (pintype "passive"))
    )
    (net (code "64") (name "unconnected-(U1-PC2{slash}ADC2-Pad25)") (class "Default")
      (node (ref "U1") (pin "25") (pinfunction "PC2/ADC2_25") (pintype "passive"))
    )
    (net (code "65") (name "unconnected-(U1-PC3{slash}ADC3-Pad26)") (class "Default")
      (node (ref "U1") (pin "26") (pinfunction "PC3/ADC3_26") (pintype "passive"))
    )
    (net (code "66") (name "unconnected-(U1-PC4{slash}ADC4{slash}SDA-Pad27)") (class "Default")
      (node (ref "U1") (pin "27") (pinfunction "PC4/ADC4/SDA_27") (pintype "passive"))
    )
    (net (code "67") (name "unconnected-(U1-PC5{slash}ADC5{slash}SCL-Pad28)") (class "Default")
      (node (ref "U1") (pin "28") (pinfunction "PC5/ADC5/SCL_28") (pintype "passive"))
    )
    (net (code "68") (name "unconnected-(U1-PD5{slash}T1{slash}OC0B-Pad9)") (class "Default")
      (node (ref "U1") (pin "9") (pinfunction "PD5/T1/OC0B_9") (pintype "passive"))
    )
    (net (code "69") (name "unconnected-(U1-PD6{slash}OC0A-Pad10)") (class "Default")
      (node (ref "U1") (pin "10") (pinfunction "PD6/OC0A_10") (pintype "passive"))
    )
    (net (code "70") (name "unconnected-(U1-PD7-Pad11)") (class "Default")
      (node (ref "U1") (pin "11") (pinfunction "PD7_11") (pintype "passive"))
    )
    (net (code "71") (name "unconnected-(U31-~{SAG}-Pad13)") (class "Default")
      (node (ref "U31") (pin "13") (pinfunction "~{SAG}_13") (pintype "passive+no_connect"))
    )
  )
)
